# HAB_APRS_V1_0.net
KiCad netlist of a schematic drawn in EAGLE
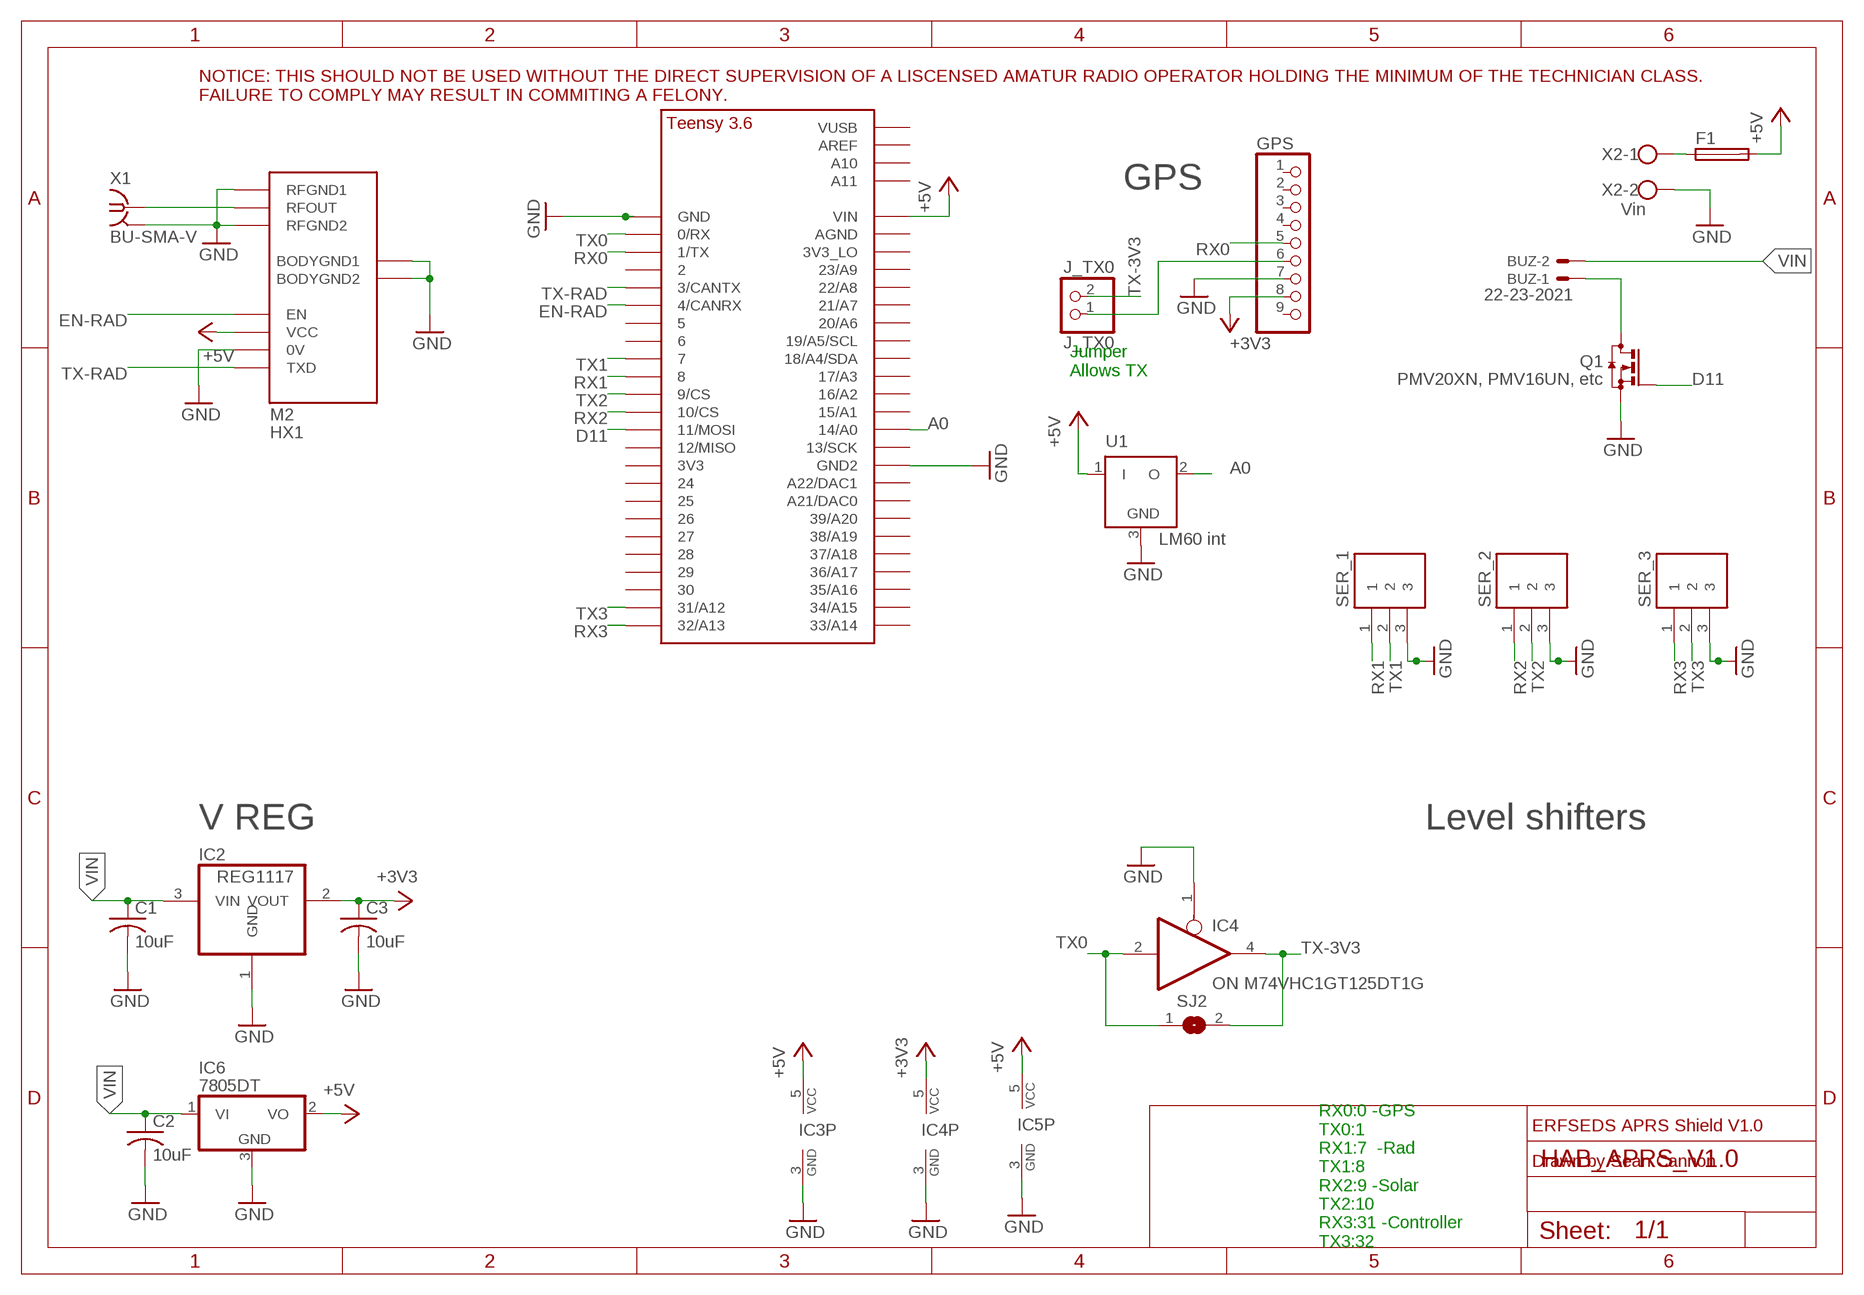
[diagram p0: schematic, sheet 1]

(export (version "E")
  (design (tool "Eeschema 10.0.6"))
  (components
    (comp (ref "BUZ")
      (value "22-23-2021")
      (footprint "eagle-import:22-23-2021")
      (fields (field (name "MF") "MOLEX"))
      (libsource (lib "eagle-import") (part "22-23-2021"))
    )
    (comp (ref "C1")
      (value "10uF")
      (footprint "eagle-import:C0805")
      (libsource (lib "eagle-import") (part "C-USC0805"))
    )
    (comp (ref "C2")
      (value "10uF")
      (footprint "eagle-import:C0805")
      (libsource (lib "eagle-import") (part "C-USC0805"))
    )
    (comp (ref "C3")
      (value "10uF")
      (footprint "eagle-import:C0805")
      (libsource (lib "eagle-import") (part "C-USC0805"))
    )
    (comp (ref "F1")
      (value "FUSE_CHIP(6126-METRIC)")
      (footprint "eagle-import:FUSC6126X294N")
      (libsource (lib "eagle-import") (part "FUSECHIP(6126-METRIC)_"))
    )
    (comp (ref "GPS")
      (value "PINHD-1X9")
      (footprint "eagle-import:1X09-BIG")
      (libsource (lib "eagle-import") (part "PINHD-1X9"))
    )
    (comp (ref "IC2")
      (value "REG1117")
      (footprint "eagle-import:SOT223")
      (libsource (lib "eagle-import") (part "REG1117"))
    )
    (comp (ref "IC3")
      (value "ON M74VHC1GT125DT1G")
      (footprint "eagle-import:SOT23-5")
      (libsource (lib "eagle-import") (part "741G125DBVAHC"))
    )
    (comp (ref "IC4")
      (value "ON M74VHC1GT125DT1G")
      (footprint "eagle-import:SOT23-5")
      (libsource (lib "eagle-import") (part "741G125DBVAHC"))
    )
    (comp (ref "IC5")
      (value "ON M74VHC1GT125DT1G")
      (footprint "eagle-import:SOT23-5")
      (libsource (lib "eagle-import") (part "741G125DBVAHC"))
    )
    (comp (ref "IC6")
      (value "7805DT")
      (footprint "eagle-import:TO252")
      (libsource (lib "eagle-import") (part "78DT05"))
    )
    (comp (ref "J_TX0")
      (value "J_TX0")
      (footprint "eagle-import:1X02")
      (libsource (lib "eagle-import") (part "PINHD-1X2"))
    )
    (comp (ref "M2")
      (value "HX1")
      (footprint "eagle-import:HX1")
      (libsource (lib "eagle-import") (part "HX1"))
    )
    (comp (ref "Q1")
      (value "PMV20XN, PMV16UN, etc")
      (footprint "eagle-import:SOT23")
      (libsource (lib "eagle-import") (part "BSS123"))
    )
    (comp (ref "SER_1")
      (value "MOLEX_SL_03-70551")
      (footprint "eagle-import:SL_70551_3")
      (libsource (lib "eagle-import") (part "MOLEX_SL_03-70551"))
    )
    (comp (ref "SER_2")
      (value "MOLEX_SL_03-70551")
      (footprint "eagle-import:SL_70551_3")
      (libsource (lib "eagle-import") (part "MOLEX_SL_03-70551"))
    )
    (comp (ref "SER_3")
      (value "MOLEX_SL_03-70551")
      (footprint "eagle-import:SL_70551_3")
      (libsource (lib "eagle-import") (part "MOLEX_SL_03-70551"))
    )
    (comp (ref "SJ2") (value "SJ") (footprint "eagle-import:SJ") (libsource (lib "eagle-import") (part "SJ")))
    (comp (ref "U$1")
      (value "TEENSY_3.5/3.6_BASIC")
      (footprint "eagle-import:TEENSY_3.5_3.6_BASIC")
      (libsource (lib "eagle-import") (part "TEENSY_3.5/3.6_BASIC"))
    )
    (comp (ref "U1")
      (value "LM60 int")
      (footprint "eagle-import:TO92")
      (libsource (lib "eagle-import") (part "LM60"))
    )
    (comp (ref "X1")
      (value "BU-SMA-V")
      (footprint "eagle-import:BU-SMA-V")
      (libsource (lib "eagle-import") (part "BU-SMA-V"))
    )
    (comp (ref "X2")
      (value "Vin")
      (footprint "eagle-import:W237-102")
      (fields (field (name "MPN") "237-102"))
      (libsource (lib "eagle-import") (part "W237-102"))
    )
  )
  (nets
    (net (code "1") (name "+3V3") (class "Default")
      (node (ref "C3") (pin "1") (pinfunction "1_1") (pintype "passive"))
      (node (ref "GPS") (pin "8") (pinfunction "8_8") (pintype "passive"))
      (node (ref "IC2") (pin "2") (pinfunction "VOUT_2") (pintype "output"))
      (node (ref "IC4") (pin "5") (pinfunction "VCC_5") (pintype "power_in"))
    )
    (net (code "2") (name "+5V") (class "Default")
      (node (ref "F1") (pin "2") (pinfunction "2_2") (pintype "passive"))
      (node (ref "IC3") (pin "5") (pinfunction "VCC_5") (pintype "power_in"))
      (node (ref "IC5") (pin "5") (pinfunction "VCC_5") (pintype "power_in"))
      (node (ref "IC6") (pin "2") (pinfunction "VO_2") (pintype "passive"))
      (node (ref "M2") (pin "VCC") (pinfunction "VCC_VCC") (pintype "bidirectional"))
      (node (ref "U$1") (pin "VIN") (pinfunction "VIN_VIN") (pintype "bidirectional"))
      (node (ref "U1") (pin "1") (pinfunction "I_1") (pintype "input"))
    )
    (net (code "3") (name "/A0") (class "Default")
      (node (ref "U$1") (pin "14/A0") (pinfunction "14/A0_14/A0") (pintype "bidirectional"))
      (node (ref "U1") (pin "2") (pinfunction "O_2") (pintype "input"))
    )
    (net (code "4") (name "/D11") (class "Default")
      (node (ref "Q1") (pin "1") (pinfunction "G_1") (pintype "passive"))
      (node (ref "U$1") (pin "11/MOSI") (pinfunction "11/MOSI_11/MOSI") (pintype "bidirectional"))
    )
    (net (code "5") (name "/EN-RAD") (class "Default")
      (node (ref "M2") (pin "EN") (pinfunction "EN_EN") (pintype "bidirectional"))
      (node (ref "U$1") (pin "4/CANRX") (pinfunction "4/CANRX_4/CANRX") (pintype "bidirectional"))
    )
    (net (code "6") (name "/RX0") (class "Default")
      (node (ref "GPS") (pin "5") (pinfunction "5_5") (pintype "passive"))
      (node (ref "U$1") (pin "1/TX") (pinfunction "1/TX_1/TX") (pintype "bidirectional"))
    )
    (net (code "7") (name "/RX1") (class "Default")
      (node (ref "SER_1") (pin "1") (pinfunction "1_1") (pintype "bidirectional"))
      (node (ref "U$1") (pin "8") (pinfunction "8_8") (pintype "bidirectional"))
    )
    (net (code "8") (name "/RX2") (class "Default")
      (node (ref "SER_2") (pin "1") (pinfunction "1_1") (pintype "bidirectional"))
      (node (ref "U$1") (pin "10/CS") (pinfunction "10/CS_10/CS") (pintype "bidirectional"))
    )
    (net (code "9") (name "/RX3") (class "Default")
      (node (ref "SER_3") (pin "1") (pinfunction "1_1") (pintype "bidirectional"))
      (node (ref "U$1") (pin "32/A13") (pinfunction "32/A13_32/A13") (pintype "bidirectional"))
    )
    (net (code "10") (name "/TX-3V3") (class "Default")
      (node (ref "IC4") (pin "4") (pinfunction "O_4") (pintype "tri_state"))
      (node (ref "J_TX0") (pin "2") (pinfunction "2_2") (pintype "passive"))
      (node (ref "SJ2") (pin "2") (pinfunction "2_2") (pintype "passive"))
    )
    (net (code "11") (name "/TX-RAD") (class "Default")
      (node (ref "M2") (pin "TXD") (pinfunction "TXD_TXD") (pintype "bidirectional"))
      (node (ref "U$1") (pin "3/CANTX") (pinfunction "3/CANTX_3/CANTX") (pintype "bidirectional"))
    )
    (net (code "12") (name "/TX0") (class "Default")
      (node (ref "IC4") (pin "2") (pinfunction "I_2") (pintype "input"))
      (node (ref "SJ2") (pin "1") (pinfunction "1_1") (pintype "passive"))
      (node (ref "U$1") (pin "0/RX") (pinfunction "0/RX_0/RX") (pintype "bidirectional"))
    )
    (net (code "13") (name "/TX1") (class "Default")
      (node (ref "SER_1") (pin "2") (pinfunction "2_2") (pintype "bidirectional"))
      (node (ref "U$1") (pin "7") (pinfunction "7_7") (pintype "bidirectional"))
    )
    (net (code "14") (name "/TX2") (class "Default")
      (node (ref "SER_2") (pin "2") (pinfunction "2_2") (pintype "bidirectional"))
      (node (ref "U$1") (pin "9/CS") (pinfunction "9/CS_9/CS") (pintype "bidirectional"))
    )
    (net (code "15") (name "/TX3") (class "Default")
      (node (ref "SER_3") (pin "2") (pinfunction "2_2") (pintype "bidirectional"))
      (node (ref "U$1") (pin "31/A12") (pinfunction "31/A12_31/A12") (pintype "bidirectional"))
    )
    (net (code "16") (name "GND") (class "Default")
      (node (ref "C1") (pin "2") (pinfunction "2_2") (pintype "passive"))
      (node (ref "C2") (pin "2") (pinfunction "2_2") (pintype "passive"))
      (node (ref "C3") (pin "2") (pinfunction "2_2") (pintype "passive"))
      (node (ref "GPS") (pin "7") (pinfunction "7_7") (pintype "passive"))
      (node (ref "IC2") (pin "1") (pinfunction "GND_1") (pintype "power_in"))
      (node (ref "IC3") (pin "3") (pinfunction "GND_3") (pintype "power_in"))
      (node (ref "IC4") (pin "1") (pinfunction "OE_1") (pintype "input"))
      (node (ref "IC4") (pin "3") (pinfunction "GND_3") (pintype "power_in"))
      (node (ref "IC5") (pin "3") (pinfunction "GND_3") (pintype "power_in"))
      (node (ref "IC6") (pin "3") (pinfunction "GND_3") (pintype "passive"))
      (node (ref "M2") (pin "0V") (pinfunction "0V_0V") (pintype "bidirectional"))
      (node (ref "M2") (pin "BODYGND1") (pinfunction "BODYGND1_BODYGND1") (pintype "bidirectional"))
      (node (ref "M2") (pin "BODYGND2") (pinfunction "BODYGND2_BODYGND2") (pintype "bidirectional"))
      (node (ref "M2") (pin "RFGND1") (pinfunction "RFGND1_RFGND1") (pintype "bidirectional"))
      (node (ref "M2") (pin "RFGND2") (pinfunction "RFGND2_RFGND2") (pintype "bidirectional"))
      (node (ref "Q1") (pin "2") (pinfunction "S_2") (pintype "passive"))
      (node (ref "SER_1") (pin "3") (pinfunction "3_3") (pintype "bidirectional"))
      (node (ref "SER_2") (pin "3") (pinfunction "3_3") (pintype "bidirectional"))
      (node (ref "SER_3") (pin "3") (pinfunction "3_3") (pintype "bidirectional"))
      (node (ref "U$1") (pin "GND") (pinfunction "GND_GND") (pintype "bidirectional"))
      (node (ref "U$1") (pin "GND2") (pinfunction "GND2_GND2") (pintype "bidirectional"))
      (node (ref "U1") (pin "3") (pinfunction "GND_3") (pintype "power_in"))
      (node (ref "X1") (pin "2") (pinfunction "GND_2") (pintype "power_in"))
      (node (ref "X2") (pin "2") (pinfunction "KL_2") (pintype "passive"))
    )
    (net (code "17") (name "Net-(BUZA-S)") (class "Default")
      (node (ref "BUZ") (pin "1") (pinfunction "S_1") (pintype "passive"))
      (node (ref "Q1") (pin "3") (pinfunction "D_3") (pintype "passive"))
    )
    (net (code "18") (name "Net-(GPS-Pad6)") (class "Default")
      (node (ref "GPS") (pin "6") (pinfunction "6_6") (pintype "passive"))
      (node (ref "J_TX0") (pin "1") (pinfunction "1_1") (pintype "passive"))
    )
    (net (code "19") (name "Net-(M2-PadRFOUT)") (class "Default")
      (node (ref "M2") (pin "RFOUT") (pinfunction "RFOUT_RFOUT") (pintype "bidirectional"))
      (node (ref "X1") (pin "1") (pinfunction "1_1") (pintype "passive"))
    )
    (net (code "20") (name "Net-(X2A-KL)") (class "Default")
      (node (ref "F1") (pin "1") (pinfunction "1_1") (pintype "passive"))
      (node (ref "X2") (pin "1") (pinfunction "KL_1") (pintype "passive"))
    )
    (net (code "21") (name "VIN") (class "Default")
      (node (ref "BUZ") (pin "2") (pinfunction "S_2") (pintype "passive"))
      (node (ref "C1") (pin "1") (pinfunction "1_1") (pintype "passive"))
      (node (ref "C2") (pin "1") (pinfunction "1_1") (pintype "passive"))
      (node (ref "IC2") (pin "3") (pinfunction "VIN_3") (pintype "input"))
      (node (ref "IC6") (pin "1") (pinfunction "VI_1") (pintype "input"))
    )
    (net (code "22") (name "unconnected-(GPS-Pad1)") (class "Default")
      (node (ref "GPS") (pin "1") (pinfunction "1_1") (pintype "passive"))
    )
    (net (code "23") (name "unconnected-(GPS-Pad2)") (class "Default")
      (node (ref "GPS") (pin "2") (pinfunction "2_2") (pintype "passive"))
    )
    (net (code "24") (name "unconnected-(GPS-Pad3)") (class "Default")
      (node (ref "GPS") (pin "3") (pinfunction "3_3") (pintype "passive"))
    )
    (net (code "25") (name "unconnected-(GPS-Pad4)") (class "Default")
      (node (ref "GPS") (pin "4") (pinfunction "4_4") (pintype "passive"))
    )
    (net (code "26") (name "unconnected-(GPS-Pad9)") (class "Default")
      (node (ref "GPS") (pin "9") (pinfunction "9_9") (pintype "passive"))
    )
    (net (code "27") (name "unconnected-(U$1-A21{slash}DAC0-Pad21{slash}DAC0)") (class "Default")
      (node (ref "U$1") (pin "21/DAC0") (pinfunction "A21/DAC0_21/DAC0") (pintype "bidirectional"))
    )
    (net (code "28") (name "unconnected-(U$1-Pad2)") (class "Default")
      (node (ref "U$1") (pin "2") (pinfunction "2_2") (pintype "bidirectional"))
    )
    (net (code "29") (name "unconnected-(U$1-Pad3V3)") (class "Default")
      (node (ref "U$1") (pin "3V3") (pinfunction "3V3_3V3") (pintype "bidirectional"))
    )
    (net (code "30") (name "unconnected-(U$1-Pad3V3_LO)") (class "Default")
      (node (ref "U$1") (pin "3V3_LO") (pinfunction "3V3_LO_3V3_LO") (pintype "bidirectional"))
    )
    (net (code "31") (name "unconnected-(U$1-Pad5)") (class "Default")
      (node (ref "U$1") (pin "5") (pinfunction "5_5") (pintype "bidirectional"))
    )
    (net (code "32") (name "unconnected-(U$1-Pad6)") (class "Default")
      (node (ref "U$1") (pin "6") (pinfunction "6_6") (pintype "bidirectional"))
    )
    (net (code "33") (name "unconnected-(U$1-Pad12{slash}MISO)") (class "Default")
      (node (ref "U$1") (pin "12/MISO") (pinfunction "12/MISO_12/MISO") (pintype "bidirectional"))
    )
    (net (code "34") (name "unconnected-(U$1-Pad13{slash}SCK)") (class "Default")
      (node (ref "U$1") (pin "13/SCK") (pinfunction "13/SCK_13/SCK") (pintype "bidirectional"))
    )
    (net (code "35") (name "unconnected-(U$1-Pad15{slash}A1)") (class "Default")
      (node (ref "U$1") (pin "15/A1") (pinfunction "15/A1_15/A1") (pintype "bidirectional"))
    )
    (net (code "36") (name "unconnected-(U$1-Pad16{slash}A2)") (class "Default")
      (node (ref "U$1") (pin "16/A2") (pinfunction "16/A2_16/A2") (pintype "bidirectional"))
    )
    (net (code "37") (name "unconnected-(U$1-Pad17{slash}A3)") (class "Default")
      (node (ref "U$1") (pin "17/A3") (pinfunction "17/A3_17/A3") (pintype "bidirectional"))
    )
    (net (code "38") (name "unconnected-(U$1-Pad18{slash}A4{slash}SDA)") (class "Default")
      (node (ref "U$1") (pin "18/A4/SDA") (pinfunction "18/A4/SDA_18/A4/SDA") (pintype "bidirectional"))
    )
    (net (code "39") (name "unconnected-(U$1-Pad19{slash}A5{slash}SCL)") (class "Default")
      (node (ref "U$1") (pin "19/A5/SCL") (pinfunction "19/A5/SCL_19/A5/SCL") (pintype "bidirectional"))
    )
    (net (code "40") (name "unconnected-(U$1-Pad20{slash}A6)") (class "Default")
      (node (ref "U$1") (pin "20/A6") (pinfunction "20/A6_20/A6") (pintype "bidirectional"))
    )
    (net (code "41") (name "unconnected-(U$1-Pad21{slash}A7)") (class "Default")
      (node (ref "U$1") (pin "21/A7") (pinfunction "21/A7_21/A7") (pintype "bidirectional"))
    )
    (net (code "42") (name "unconnected-(U$1-Pad22{slash}A8)") (class "Default")
      (node (ref "U$1") (pin "22/A8") (pinfunction "22/A8_22/A8") (pintype "bidirectional"))
    )
    (net (code "43") (name "unconnected-(U$1-Pad23{slash}A9)") (class "Default")
      (node (ref "U$1") (pin "23/A9") (pinfunction "23/A9_23/A9") (pintype "bidirectional"))
    )
    (net (code "44") (name "unconnected-(U$1-Pad24)") (class "Default")
      (node (ref "U$1") (pin "24") (pinfunction "24_24") (pintype "bidirectional"))
    )
    (net (code "45") (name "unconnected-(U$1-Pad25)") (class "Default")
      (node (ref "U$1") (pin "25") (pinfunction "25_25") (pintype "bidirectional"))
    )
    (net (code "46") (name "unconnected-(U$1-Pad26)") (class "Default")
      (node (ref "U$1") (pin "26") (pinfunction "26_26") (pintype "bidirectional"))
    )
    (net (code "47") (name "unconnected-(U$1-Pad27)") (class "Default")
      (node (ref "U$1") (pin "27") (pinfunction "27_27") (pintype "bidirectional"))
    )
    (net (code "48") (name "unconnected-(U$1-Pad28)") (class "Default")
      (node (ref "U$1") (pin "28") (pinfunction "28_28") (pintype "bidirectional"))
    )
    (net (code "49") (name "unconnected-(U$1-Pad29)") (class "Default")
      (node (ref "U$1") (pin "29") (pinfunction "29_29") (pintype "bidirectional"))
    )
    (net (code "50") (name "unconnected-(U$1-Pad30)") (class "Default")
      (node (ref "U$1") (pin "30") (pinfunction "30_30") (pintype "bidirectional"))
    )
    (net (code "51") (name "unconnected-(U$1-Pad33{slash}A14)") (class "Default")
      (node (ref "U$1") (pin "33/A14") (pinfunction "33/A14_33/A14") (pintype "bidirectional"))
    )
    (net (code "52") (name "unconnected-(U$1-Pad34{slash}A15)") (class "Default")
      (node (ref "U$1") (pin "34/A15") (pinfunction "34/A15_34/A15") (pintype "bidirectional"))
    )
    (net (code "53") (name "unconnected-(U$1-Pad35{slash}A16)") (class "Default")
      (node (ref "U$1") (pin "35/A16") (pinfunction "35/A16_35/A16") (pintype "bidirectional"))
    )
    (net (code "54") (name "unconnected-(U$1-Pad36{slash}A17)") (class "Default")
      (node (ref "U$1") (pin "36/A17") (pinfunction "36/A17_36/A17") (pintype "bidirectional"))
    )
    (net (code "55") (name "unconnected-(U$1-Pad37{slash}A18)") (class "Default")
      (node (ref "U$1") (pin "37/A18") (pinfunction "37/A18_37/A18") (pintype "bidirectional"))
    )
    (net (code "56") (name "unconnected-(U$1-Pad38{slash}A19)") (class "Default")
      (node (ref "U$1") (pin "38/A19") (pinfunction "38/A19_38/A19") (pintype "bidirectional"))
    )
    (net (code "57") (name "unconnected-(U$1-Pad39{slash}A20)") (class "Default")
      (node (ref "U$1") (pin "39/A20") (pinfunction "39/A20_39/A20") (pintype "bidirectional"))
    )
    (net (code "58") (name "unconnected-(U$1-PadA10)") (class "Default")
      (node (ref "U$1") (pin "A10") (pinfunction "A10_A10") (pintype "bidirectional"))
    )
    (net (code "59") (name "unconnected-(U$1-PadA11)") (class "Default")
      (node (ref "U$1") (pin "A11") (pinfunction "A11_A11") (pintype "bidirectional"))
    )
    (net (code "60") (name "unconnected-(U$1-PadA22{slash}DAC1)") (class "Default")
      (node (ref "U$1") (pin "A22/DAC1") (pinfunction "A22/DAC1_A22/DAC1") (pintype "bidirectional"))
    )
    (net (code "61") (name "unconnected-(U$1-PadAGND)") (class "Default")
      (node (ref "U$1") (pin "AGND") (pinfunction "AGND_AGND") (pintype "bidirectional"))
    )
    (net (code "62") (name "unconnected-(U$1-PadAREF)") (class "Default")
      (node (ref "U$1") (pin "AREF") (pinfunction "AREF_AREF") (pintype "bidirectional"))
    )
    (net (code "63") (name "unconnected-(U$1-PadVUSB)") (class "Default")
      (node (ref "U$1") (pin "VUSB") (pinfunction "VUSB_VUSB") (pintype "bidirectional"))
    )
  )
)
